# Base.net
KiCad netlist of a schematic drawn in EAGLE
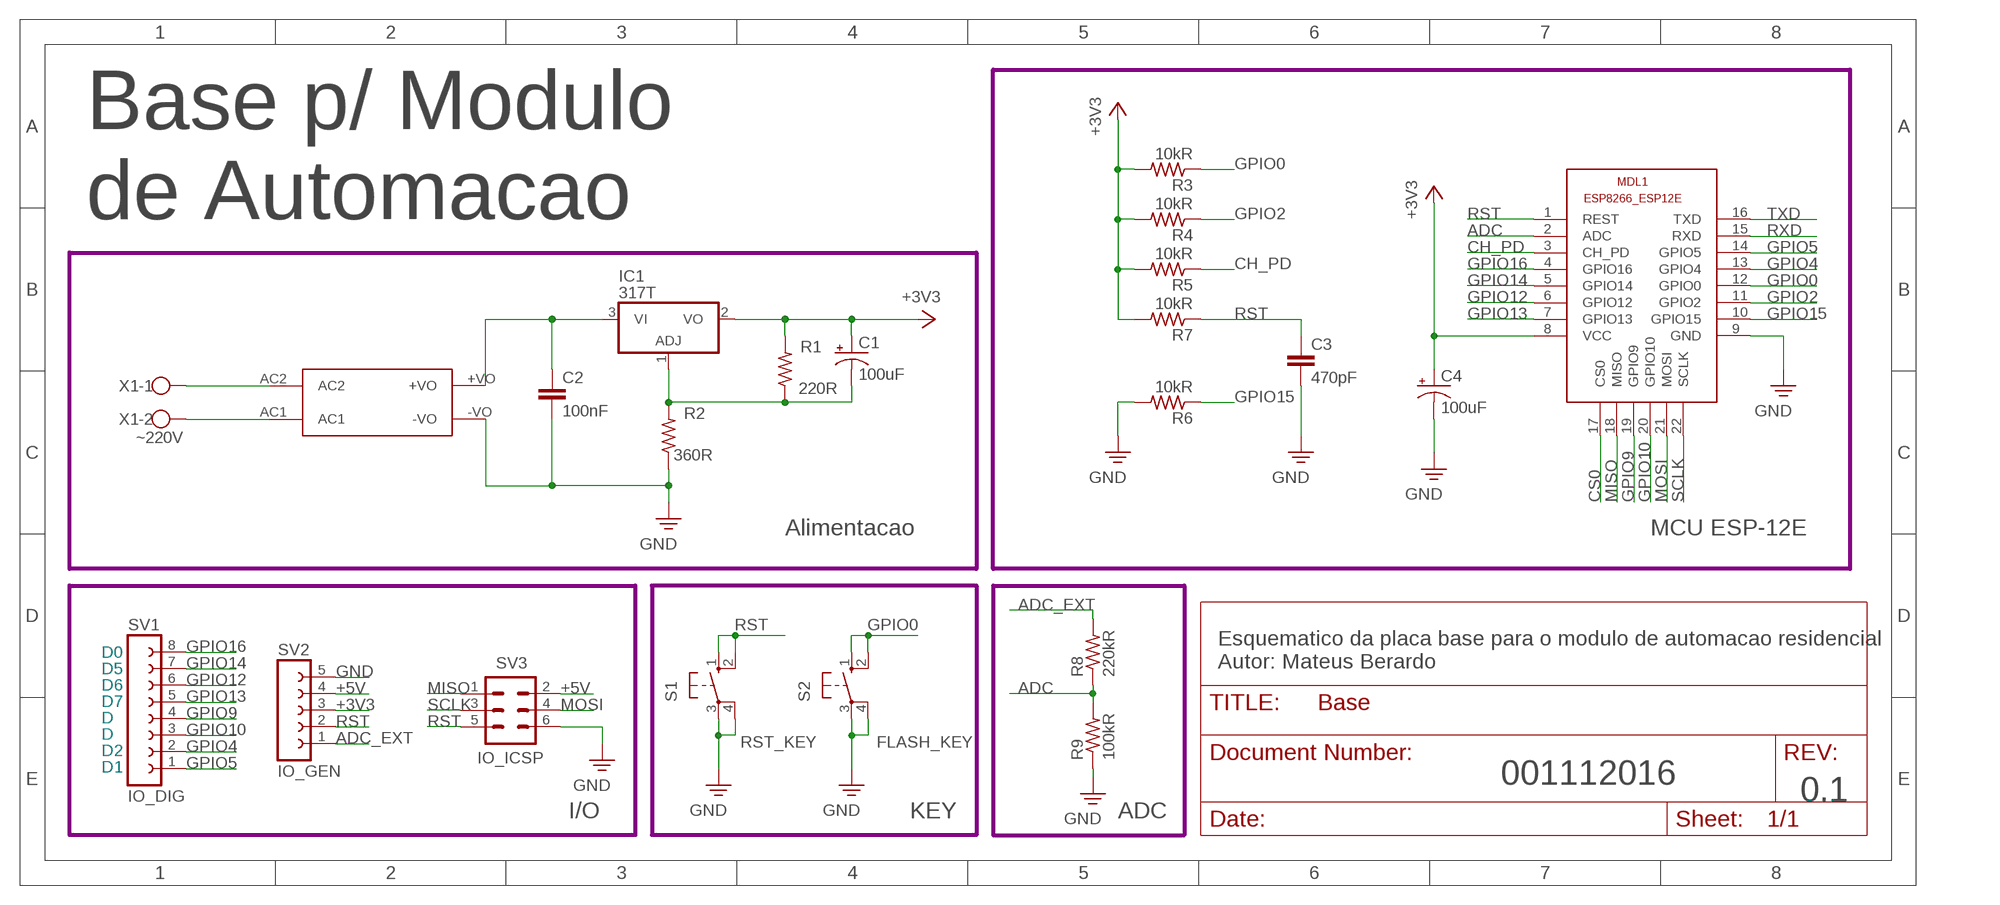
[diagram p0: schematic, sheet 1]

(export (version "E")
  (design (tool "Eeschema 10.0.6"))
  (components
    (comp (ref "C1")
      (value "100uF")
      (footprint "eagle-import:E3,5-8")
      (libsource (lib "eagle-import") (part "CPOL-USE3.5-8"))
    )
    (comp (ref "C2")
      (value "100nF")
      (footprint "eagle-import:C050-055X075")
      (libsource (lib "eagle-import") (part "C-EU050-055X075"))
    )
    (comp (ref "C3")
      (value "470pF")
      (footprint "eagle-import:C050-055X075")
      (libsource (lib "eagle-import") (part "C-EU050-055X075"))
    )
    (comp (ref "C4")
      (value "100uF")
      (footprint "eagle-import:E3,5-8")
      (libsource (lib "eagle-import") (part "CPOL-USE3.5-8"))
    )
    (comp (ref "IC1")
      (value "317T")
      (footprint "eagle-import:TO220H")
      (libsource (lib "eagle-import") (part "317T"))
    )
    (comp (ref "MDL1")
      (value "MCU ESP")
      (footprint "eagle-import:ESP8266-ESP12E")
      (libsource (lib "eagle-import") (part "ESP8266-12EESP8266-ESP12E"))
    )
    (comp (ref "R1")
      (value "220R")
      (footprint "eagle-import:0207_10")
      (libsource (lib "eagle-import") (part "R-US_0207/10"))
    )
    (comp (ref "R2")
      (value "360R")
      (footprint "eagle-import:0207_10")
      (libsource (lib "eagle-import") (part "R-US_0207/10"))
    )
    (comp (ref "R3")
      (value "10kR")
      (footprint "eagle-import:0207_10")
      (libsource (lib "eagle-import") (part "R-US_0207/10"))
    )
    (comp (ref "R4")
      (value "10kR")
      (footprint "eagle-import:0207_10")
      (libsource (lib "eagle-import") (part "R-US_0207/10"))
    )
    (comp (ref "R5")
      (value "10kR")
      (footprint "eagle-import:0207_10")
      (libsource (lib "eagle-import") (part "R-US_0207/10"))
    )
    (comp (ref "R6")
      (value "10kR")
      (footprint "eagle-import:0207_10")
      (libsource (lib "eagle-import") (part "R-US_0207/10"))
    )
    (comp (ref "R7")
      (value "10kR")
      (footprint "eagle-import:0207_10")
      (libsource (lib "eagle-import") (part "R-US_0207/10"))
    )
    (comp (ref "R8")
      (value "220kR")
      (footprint "eagle-import:0207_10")
      (libsource (lib "eagle-import") (part "R-US_0207/10"))
    )
    (comp (ref "R9")
      (value "100kR")
      (footprint "eagle-import:0207_10")
      (libsource (lib "eagle-import") (part "R-US_0207/10"))
    )
    (comp (ref "S1")
      (value "RST_KEY")
      (footprint "eagle-import:B3F-10XX")
      (fields (field (name "MPN") "B3F-1000"))
      (libsource (lib "eagle-import") (part "10-XX"))
    )
    (comp (ref "S2")
      (value "FLASH_KEY")
      (footprint "eagle-import:B3F-10XX")
      (fields (field (name "MPN") "B3F-1000"))
      (libsource (lib "eagle-import") (part "10-XX"))
    )
    (comp (ref "SV1")
      (value "IO_DIG")
      (footprint "eagle-import:FE08")
      (libsource (lib "eagle-import") (part "FE08-1"))
    )
    (comp (ref "SV2")
      (value "IO_GEN")
      (footprint "eagle-import:FE05-1")
      (libsource (lib "eagle-import") (part "FE05-1"))
    )
    (comp (ref "SV3")
      (value "IO_ICSP")
      (footprint "eagle-import:MA03-2")
      (libsource (lib "eagle-import") (part "MA03-2"))
    )
    (comp (ref "U$1")
      (value "HLK-PM01")
      (footprint "eagle-import:HLK-PM01")
      (libsource (lib "eagle-import") (part "HLK-PM01"))
    )
    (comp (ref "X1")
      (value "~220V")
      (footprint "eagle-import:W237-102")
      (fields (field (name "MPN") "237-102"))
      (libsource (lib "eagle-import") (part "W237-102"))
    )
  )
  (nets
    (net (code "1") (name "+3V3") (class "Default")
      (node (ref "C1") (pin "+") (pinfunction "+_+") (pintype "passive"))
      (node (ref "C4") (pin "+") (pinfunction "+_+") (pintype "passive"))
      (node (ref "IC1") (pin "2") (pinfunction "VO_2") (pintype "passive"))
      (node (ref "MDL1") (pin "8") (pinfunction "VCC_8") (pintype "bidirectional"))
      (node (ref "R1") (pin "2") (pinfunction "2_2") (pintype "passive"))
      (node (ref "R3") (pin "2") (pinfunction "2_2") (pintype "passive"))
      (node (ref "R4") (pin "2") (pinfunction "2_2") (pintype "passive"))
      (node (ref "R5") (pin "2") (pinfunction "2_2") (pintype "passive"))
      (node (ref "R7") (pin "2") (pinfunction "2_2") (pintype "passive"))
      (node (ref "SV2") (pin "3") (pinfunction "3_3") (pintype "passive"))
    )
    (net (code "2") (name "/+5V") (class "Default")
      (node (ref "C2") (pin "1") (pinfunction "1_1") (pintype "passive"))
      (node (ref "IC1") (pin "3") (pinfunction "VI_3") (pintype "input"))
      (node (ref "SV2") (pin "4") (pinfunction "4_4") (pintype "passive"))
      (node (ref "SV3") (pin "2") (pinfunction "2_2") (pintype "passive"))
      (node (ref "U$1") (pin "+VO") (pinfunction "+VO_+VO") (pintype "bidirectional"))
    )
    (net (code "3") (name "/ADC") (class "Default")
      (node (ref "MDL1") (pin "2") (pinfunction "ADC_2") (pintype "bidirectional"))
      (node (ref "R8") (pin "1") (pinfunction "1_1") (pintype "passive"))
      (node (ref "R9") (pin "2") (pinfunction "2_2") (pintype "passive"))
    )
    (net (code "4") (name "/ADC_EXT") (class "Default")
      (node (ref "R8") (pin "2") (pinfunction "2_2") (pintype "passive"))
      (node (ref "SV2") (pin "1") (pinfunction "1_1") (pintype "passive"))
    )
    (net (code "5") (name "/CH_PD") (class "Default")
      (node (ref "MDL1") (pin "3") (pinfunction "CH_PD_3") (pintype "bidirectional"))
      (node (ref "R5") (pin "1") (pinfunction "1_1") (pintype "passive"))
    )
    (net (code "6") (name "/CS0") (class "Default")
      (node (ref "MDL1") (pin "17") (pinfunction "CS0_17") (pintype "bidirectional"))
    )
    (net (code "7") (name "/GPIO0") (class "Default")
      (node (ref "MDL1") (pin "12") (pinfunction "GPIO0_12") (pintype "bidirectional"))
      (node (ref "R3") (pin "1") (pinfunction "1_1") (pintype "passive"))
      (node (ref "S2") (pin "1") (pinfunction "S_1") (pintype "passive"))
      (node (ref "S2") (pin "2") (pinfunction "S1_2") (pintype "passive"))
    )
    (net (code "8") (name "/GPIO2") (class "Default")
      (node (ref "MDL1") (pin "11") (pinfunction "GPIO2_11") (pintype "bidirectional"))
      (node (ref "R4") (pin "1") (pinfunction "1_1") (pintype "passive"))
    )
    (net (code "9") (name "/GPIO4") (class "Default")
      (node (ref "MDL1") (pin "13") (pinfunction "GPIO4_13") (pintype "bidirectional"))
      (node (ref "SV1") (pin "2") (pinfunction "2_2") (pintype "passive"))
    )
    (net (code "10") (name "/GPIO5") (class "Default")
      (node (ref "MDL1") (pin "14") (pinfunction "GPIO5_14") (pintype "bidirectional"))
      (node (ref "SV1") (pin "1") (pinfunction "1_1") (pintype "passive"))
    )
    (net (code "11") (name "/GPIO9") (class "Default")
      (node (ref "MDL1") (pin "19") (pinfunction "GPIO9_19") (pintype "bidirectional"))
      (node (ref "SV1") (pin "4") (pinfunction "4_4") (pintype "passive"))
    )
    (net (code "12") (name "/GPIO10") (class "Default")
      (node (ref "MDL1") (pin "20") (pinfunction "GPIO10_20") (pintype "bidirectional"))
      (node (ref "SV1") (pin "3") (pinfunction "3_3") (pintype "passive"))
    )
    (net (code "13") (name "/GPIO12") (class "Default")
      (node (ref "MDL1") (pin "6") (pinfunction "GPIO12_6") (pintype "bidirectional"))
      (node (ref "SV1") (pin "6") (pinfunction "6_6") (pintype "passive"))
    )
    (net (code "14") (name "/GPIO13") (class "Default")
      (node (ref "MDL1") (pin "7") (pinfunction "GPIO13_7") (pintype "bidirectional"))
      (node (ref "SV1") (pin "5") (pinfunction "5_5") (pintype "passive"))
    )
    (net (code "15") (name "/GPIO14") (class "Default")
      (node (ref "MDL1") (pin "5") (pinfunction "GPIO14_5") (pintype "bidirectional"))
      (node (ref "SV1") (pin "7") (pinfunction "7_7") (pintype "passive"))
    )
    (net (code "16") (name "/GPIO15") (class "Default")
      (node (ref "MDL1") (pin "10") (pinfunction "GPIO15_10") (pintype "bidirectional"))
      (node (ref "R6") (pin "1") (pinfunction "1_1") (pintype "passive"))
    )
    (net (code "17") (name "/GPIO16") (class "Default")
      (node (ref "MDL1") (pin "4") (pinfunction "GPIO16_4") (pintype "bidirectional"))
      (node (ref "SV1") (pin "8") (pinfunction "8_8") (pintype "passive"))
    )
    (net (code "18") (name "/MISO") (class "Default")
      (node (ref "MDL1") (pin "18") (pinfunction "MISO_18") (pintype "bidirectional"))
      (node (ref "SV3") (pin "1") (pinfunction "1_1") (pintype "passive"))
    )
    (net (code "19") (name "/MOSI") (class "Default")
      (node (ref "MDL1") (pin "21") (pinfunction "MOSI_21") (pintype "bidirectional"))
      (node (ref "SV3") (pin "4") (pinfunction "4_4") (pintype "passive"))
    )
    (net (code "20") (name "/RST") (class "Default")
      (node (ref "C3") (pin "1") (pinfunction "1_1") (pintype "passive"))
      (node (ref "MDL1") (pin "1") (pinfunction "REST_1") (pintype "bidirectional"))
      (node (ref "R7") (pin "1") (pinfunction "1_1") (pintype "passive"))
      (node (ref "S1") (pin "1") (pinfunction "S_1") (pintype "passive"))
      (node (ref "S1") (pin "2") (pinfunction "S1_2") (pintype "passive"))
      (node (ref "SV2") (pin "2") (pinfunction "2_2") (pintype "passive"))
      (node (ref "SV3") (pin "5") (pinfunction "5_5") (pintype "passive"))
    )
    (net (code "21") (name "/RXD") (class "Default")
      (node (ref "MDL1") (pin "15") (pinfunction "RXD_15") (pintype "bidirectional"))
    )
    (net (code "22") (name "/SCLK") (class "Default")
      (node (ref "MDL1") (pin "22") (pinfunction "SCLK_22") (pintype "bidirectional"))
      (node (ref "SV3") (pin "3") (pinfunction "3_3") (pintype "passive"))
    )
    (net (code "23") (name "/TXD") (class "Default")
      (node (ref "MDL1") (pin "16") (pinfunction "TXD_16") (pintype "bidirectional"))
    )
    (net (code "24") (name "GND") (class "Default")
      (node (ref "C2") (pin "2") (pinfunction "2_2") (pintype "passive"))
      (node (ref "C3") (pin "2") (pinfunction "2_2") (pintype "passive"))
      (node (ref "C4") (pin "-") (pinfunction "-_-") (pintype "passive"))
      (node (ref "MDL1") (pin "9") (pinfunction "GND_9") (pintype "bidirectional"))
      (node (ref "R2") (pin "1") (pinfunction "1_1") (pintype "passive"))
      (node (ref "R6") (pin "2") (pinfunction "2_2") (pintype "passive"))
      (node (ref "R9") (pin "1") (pinfunction "1_1") (pintype "passive"))
      (node (ref "S1") (pin "3") (pinfunction "P_3") (pintype "passive"))
      (node (ref "S1") (pin "4") (pinfunction "P1_4") (pintype "passive"))
      (node (ref "S2") (pin "3") (pinfunction "P_3") (pintype "passive"))
      (node (ref "S2") (pin "4") (pinfunction "P1_4") (pintype "passive"))
      (node (ref "SV2") (pin "5") (pinfunction "5_5") (pintype "passive"))
      (node (ref "SV3") (pin "6") (pinfunction "6_6") (pintype "passive"))
      (node (ref "U$1") (pin "-VO") (pinfunction "-VO_-VO") (pintype "bidirectional"))
    )
    (net (code "25") (name "Net-(IC1-ADJ)") (class "Default")
      (node (ref "C1") (pin "-") (pinfunction "-_-") (pintype "passive"))
      (node (ref "IC1") (pin "1") (pinfunction "ADJ_1") (pintype "input"))
      (node (ref "R1") (pin "1") (pinfunction "1_1") (pintype "passive"))
      (node (ref "R2") (pin "2") (pinfunction "2_2") (pintype "passive"))
    )
    (net (code "26") (name "Net-(X1A-KL)") (class "Default")
      (node (ref "U$1") (pin "AC2") (pinfunction "AC2_AC2") (pintype "bidirectional"))
      (node (ref "X1") (pin "1") (pinfunction "KL_1") (pintype "passive"))
    )
    (net (code "27") (name "Net-(X1B-KL)") (class "Default")
      (node (ref "U$1") (pin "AC1") (pinfunction "AC1_AC1") (pintype "bidirectional"))
      (node (ref "X1") (pin "2") (pinfunction "KL_2") (pintype "passive"))
    )
  )
)
